# Power.net
KiCad netlist of a schematic drawn in Altium Designer
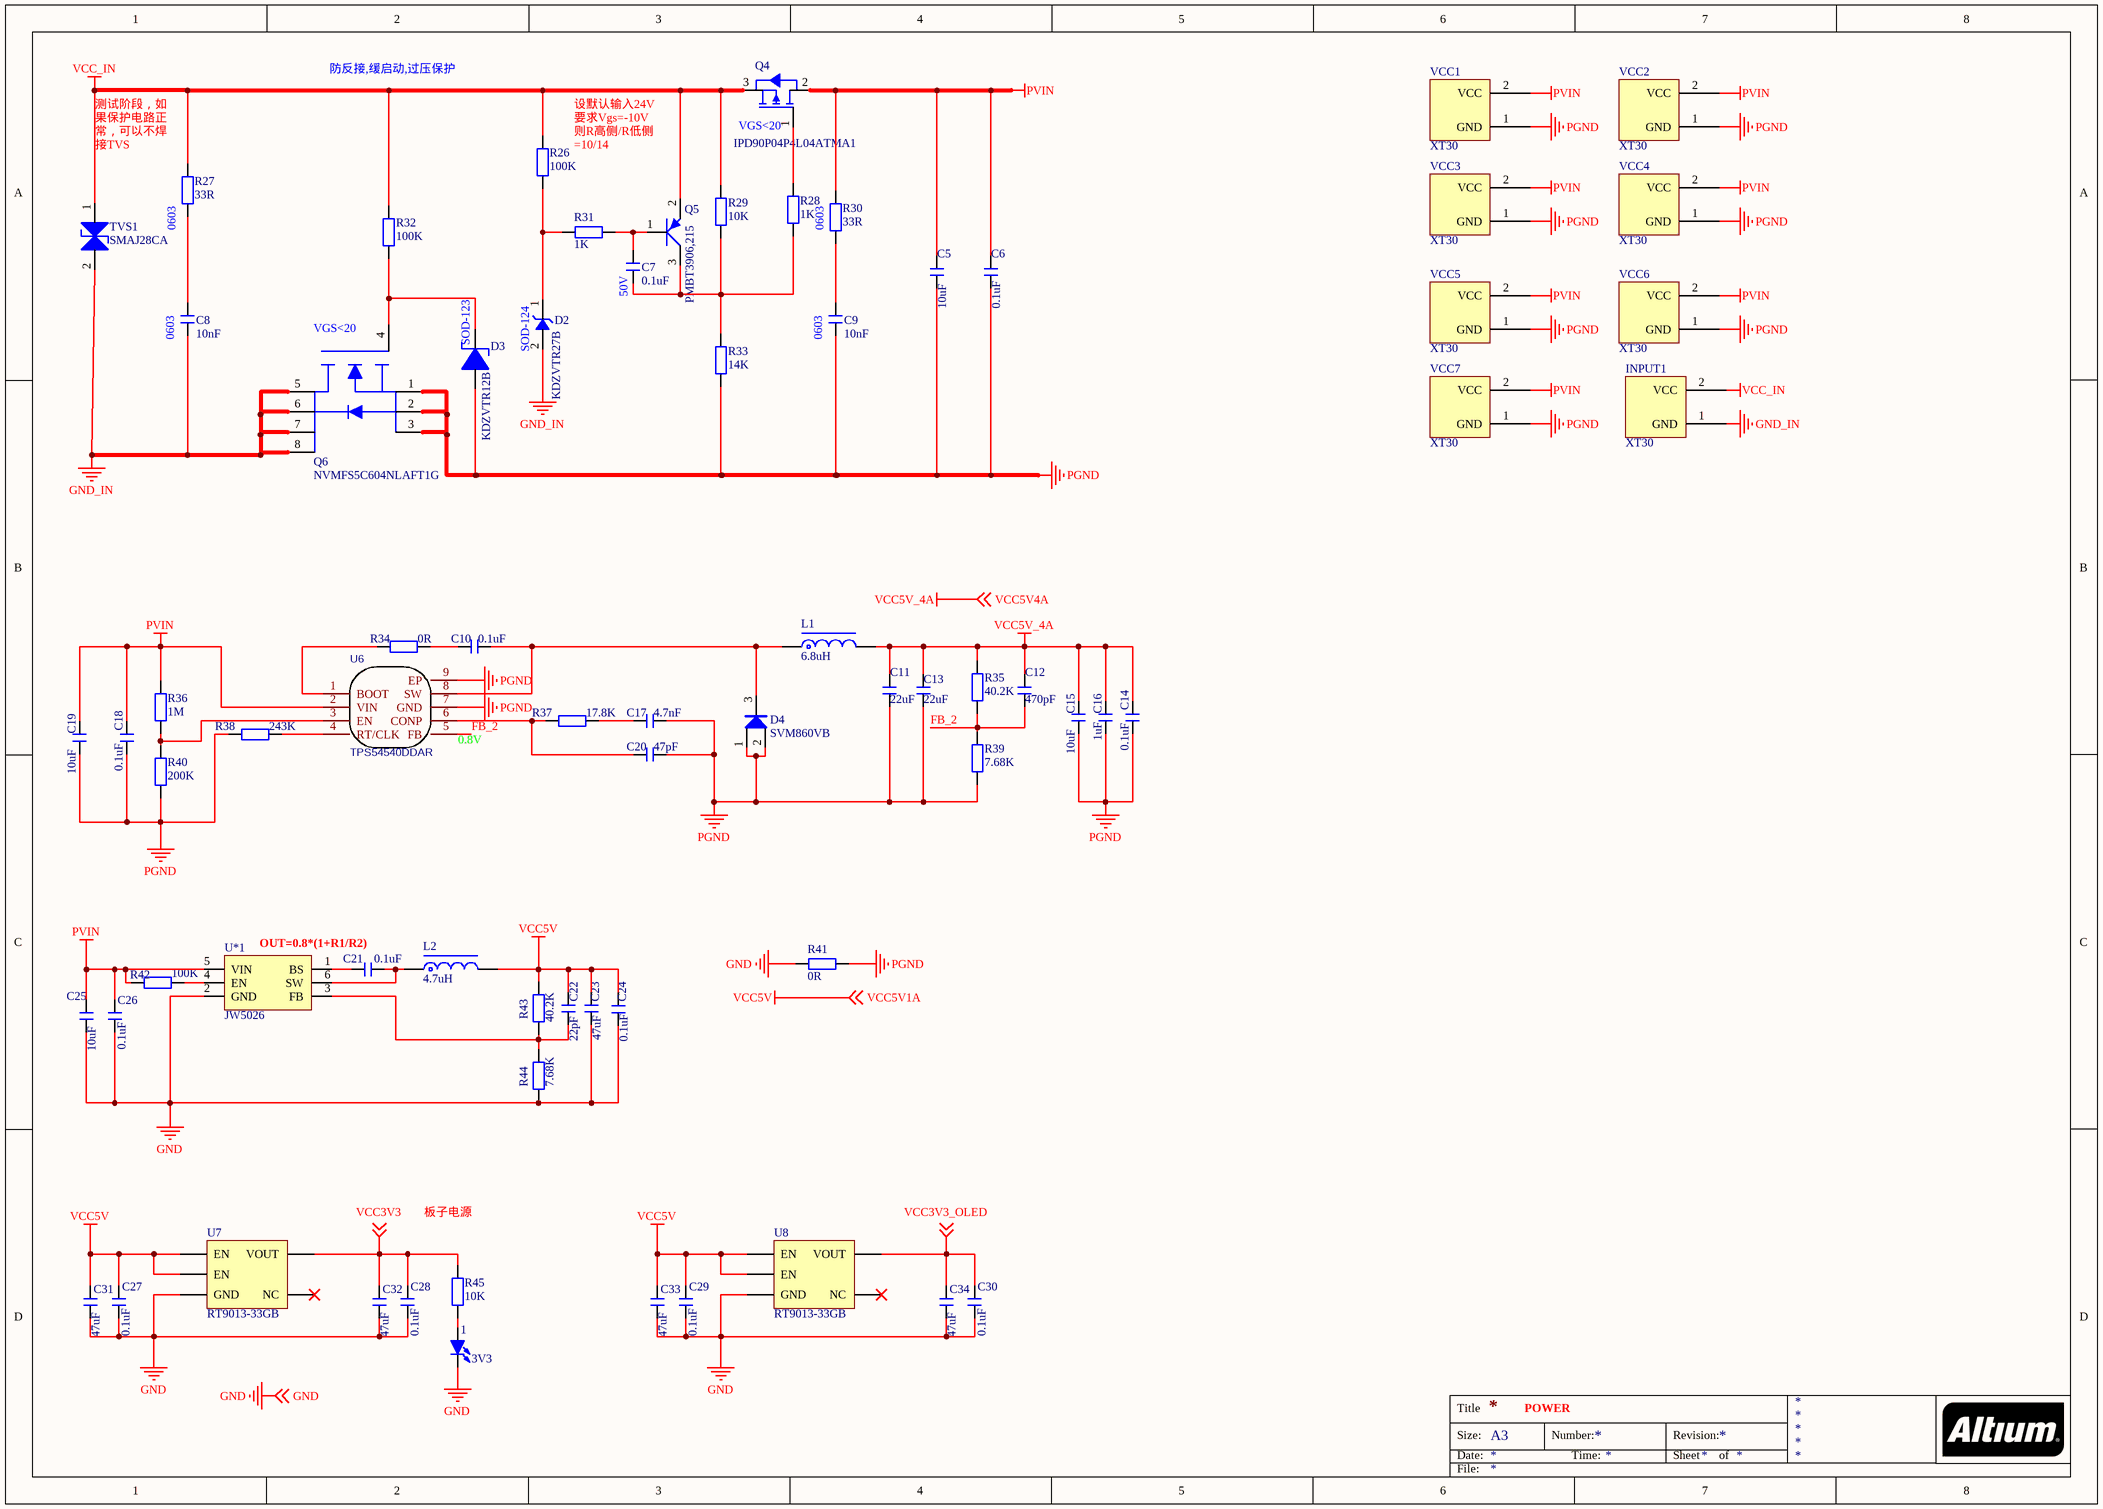
[diagram p0: Power.SchDoc]

(export (version "E")
  (design (tool "Eeschema 10.0.6"))
  (components
    (comp (ref "1")
      (value "3V3")
      (footprint "LED 0805R")
      (description "贴片LED")
      (libsource (lib "0.3 - LED发光二极管") (part "LED-SMD"))
    )
    (comp (ref "C5")
      (value "10uF")
      (footprint "C 0805_L")
      (description "贴片电容")
      (libsource (lib "0.1 - 电阻-电容-电感") (part "C"))
    )
    (comp (ref "C6")
      (value "0.1uF")
      (footprint "C 0805_L")
      (description "贴片电容")
      (libsource (lib "0.1 - 电阻-电容-电感") (part "C"))
    )
    (comp (ref "C7")
      (value "0.1uF")
      (footprint "C 0402_L")
      (description "贴片电容")
      (libsource (lib "0.1 - 电阻-电容-电感") (part "C"))
    )
    (comp (ref "C8")
      (value "10nF")
      (footprint "C 0402_L")
      (description "贴片电容")
      (libsource (lib "0.1 - 电阻-电容-电感") (part "C"))
    )
    (comp (ref "C9")
      (value "10nF")
      (footprint "C 0402_L")
      (description "贴片电容")
      (libsource (lib "0.1 - 电阻-电容-电感") (part "C"))
    )
    (comp (ref "C10")
      (value "0.1uF")
      (footprint "C 0402_L")
      (description "贴片电容")
      (libsource (lib "0.1 - 电阻-电容-电感") (part "C"))
    )
    (comp (ref "C11")
      (value "22uF")
      (footprint "C 0805_L")
      (description "贴片电容")
      (libsource (lib "0.1 - 电阻-电容-电感") (part "C"))
    )
    (comp (ref "C12")
      (value "470pF")
      (footprint "C 0402_L")
      (description "贴片电容")
      (libsource (lib "0.1 - 电阻-电容-电感") (part "C"))
    )
    (comp (ref "C13")
      (value "22uF")
      (footprint "C 0805_L")
      (description "贴片电容")
      (libsource (lib "0.1 - 电阻-电容-电感") (part "C"))
    )
    (comp (ref "C14")
      (value "0.1uF")
      (footprint "C 0805_L")
      (description "贴片电容")
      (libsource (lib "0.1 - 电阻-电容-电感") (part "C"))
    )
    (comp (ref "C15")
      (value "10uF")
      (footprint "C 0805_L")
      (description "贴片电容")
      (libsource (lib "0.1 - 电阻-电容-电感") (part "C"))
    )
    (comp (ref "C16")
      (value "1uF")
      (footprint "C 0805_L")
      (description "贴片电容")
      (libsource (lib "0.1 - 电阻-电容-电感") (part "C"))
    )
    (comp (ref "C17")
      (value "4.7nF")
      (footprint "C 0402_L")
      (description "贴片电容")
      (libsource (lib "0.1 - 电阻-电容-电感") (part "C"))
    )
    (comp (ref "C18")
      (value "0.1uF")
      (footprint "C 0805_L")
      (description "贴片电容")
      (libsource (lib "0.1 - 电阻-电容-电感") (part "C"))
    )
    (comp (ref "C19")
      (value "10uF")
      (footprint "C 0805_L")
      (description "贴片电容")
      (libsource (lib "0.1 - 电阻-电容-电感") (part "C"))
    )
    (comp (ref "C20")
      (value "47pF")
      (footprint "C 0402_L")
      (description "贴片电容")
      (libsource (lib "0.1 - 电阻-电容-电感") (part "C"))
    )
    (comp (ref "C21")
      (value "0.1uF")
      (footprint "C 0402_L")
      (description "贴片电容")
      (libsource (lib "0.1 - 电阻-电容-电感") (part "C"))
    )
    (comp (ref "C22")
      (value "22pF")
      (footprint "C 0402_L")
      (description "贴片电容")
      (libsource (lib "0.1 - 电阻-电容-电感") (part "C"))
    )
    (comp (ref "C23")
      (value "47uF")
      (footprint "C 0805_L")
      (description "贴片电容")
      (libsource (lib "0.1 - 电阻-电容-电感") (part "C"))
    )
    (comp (ref "C24")
      (value "0.1uF")
      (footprint "C 0805_L")
      (description "贴片电容")
      (libsource (lib "0.1 - 电阻-电容-电感") (part "C"))
    )
    (comp (ref "C25")
      (value "10uF")
      (footprint "C 0805_L")
      (description "贴片电容")
      (libsource (lib "0.1 - 电阻-电容-电感") (part "C"))
    )
    (comp (ref "C26")
      (value "0.1uF")
      (footprint "C 0805_L")
      (description "贴片电容")
      (libsource (lib "0.1 - 电阻-电容-电感") (part "C"))
    )
    (comp (ref "C27")
      (value "0.1uF")
      (footprint "C 0805_L")
      (description "贴片电容")
      (libsource (lib "0.1 - 电阻-电容-电感") (part "C"))
    )
    (comp (ref "C28")
      (value "0.1uF")
      (footprint "C 0805_L")
      (description "贴片电容")
      (libsource (lib "0.1 - 电阻-电容-电感") (part "C"))
    )
    (comp (ref "C29")
      (value "0.1uF")
      (footprint "C 0805_L")
      (description "贴片电容")
      (libsource (lib "0.1 - 电阻-电容-电感") (part "C"))
    )
    (comp (ref "C30")
      (value "0.1uF")
      (footprint "C 0805_L")
      (description "贴片电容")
      (libsource (lib "0.1 - 电阻-电容-电感") (part "C"))
    )
    (comp (ref "C31")
      (value "47uF")
      (footprint "C 0805_L")
      (description "贴片电容")
      (libsource (lib "0.1 - 电阻-电容-电感") (part "C"))
    )
    (comp (ref "C32")
      (value "47uF")
      (footprint "C 0805_L")
      (description "贴片电容")
      (libsource (lib "0.1 - 电阻-电容-电感") (part "C"))
    )
    (comp (ref "C33")
      (value "47uF")
      (footprint "C 0805_L")
      (description "贴片电容")
      (libsource (lib "0.1 - 电阻-电容-电感") (part "C"))
    )
    (comp (ref "C34")
      (value "47uF")
      (footprint "C 0805_L")
      (description "贴片电容")
      (libsource (lib "0.1 - 电阻-电容-电感") (part "C"))
    )
    (comp (ref "D2")
      (value "KDZVTR27B")
      (footprint "mx_pcb_library:SOD-123_L2.8-W1.8-LS3.7-RD")
      (libsource (lib "mx_pcb_library") (part "BZD27C30P"))
    )
    (comp (ref "D3")
      (value "KDZVTR12B")
      (footprint "mx_pcb_library:SOD-123_L2.8-W1.8-LS3.7-RD")
      (libsource (lib "mx_pcb_library") (part "KDZVTR12B"))
    )
    (comp (ref "D4")
      (value "SVM860VB")
      (footprint "1.30-二极管-整流桥堆:TO-277B_3P-L6.1-W4.3-LS7.0-BR")
      (description "TO-277B系列,SVM860VB-8A")
      (libsource (lib "0.2 -  二极管-整流桥") (part "SVM860VB"))
    )
    (comp (ref "INPUT1")
      (value "XT30")
      (footprint "mx_pcb_library:XT30PW-M")
      (libsource (lib "mx_pcb_library") (part "XT30"))
    )
    (comp (ref "L1")
      (value "6.8uH")
      (footprint "CDRH73")
      (description "功率屏蔽电感")
      (libsource (lib "0.1 - 电阻-电容-电感") (part "L-CDRH"))
    )
    (comp (ref "L2")
      (value "4.7uH")
      (footprint "CD53")
      (description "CD系列贴片线绕功率电感")
      (libsource (lib "0.1 - 电阻-电容-电感") (part "L-SMD"))
    )
    (comp (ref "Q4")
      (value "IPD90P04P4L04ATMA1")
      (footprint "mx_pcb_library:PG-TO252-3")
      (libsource (lib "mx_pcb_library") (part "IPD90P04P4"))
    )
    (comp (ref "Q5")
      (value "PMBT3906,215")
      (footprint "mx_pcb_library:SOT-23-3_L2.9-W1.3-P1.90-LS2.4-BR")
      (libsource (lib "mx_pcb_library") (part "PMBT3906,215"))
    )
    (comp (ref "Q6")
      (value "NVMFS5C604NLAFT1G")
      (footprint "mx_pcb_library:PG-TDSON-8_L5.0-W6.0-P1.27-LS6.2-BL-EP")
      (libsource (lib "mx_pcb_library") (part "BSC037N08NS5ATMA1"))
    )
    (comp (ref "R26")
      (value "100K")
      (footprint "R 0402_L")
      (description "贴片电阻")
      (libsource (lib "0.1 - 电阻-电容-电感") (part "R"))
    )
    (comp (ref "R27")
      (value "33R")
      (footprint "R 0402_L")
      (description "贴片电阻")
      (libsource (lib "0.1 - 电阻-电容-电感") (part "R"))
    )
    (comp (ref "R28")
      (value "1K")
      (footprint "R 0402_L")
      (description "贴片电阻")
      (libsource (lib "0.1 - 电阻-电容-电感") (part "R"))
    )
    (comp (ref "R29")
      (value "10K")
      (footprint "R 0402_L")
      (description "贴片电阻")
      (libsource (lib "0.1 - 电阻-电容-电感") (part "R"))
    )
    (comp (ref "R30")
      (value "33R")
      (footprint "R 0402_L")
      (description "贴片电阻")
      (libsource (lib "0.1 - 电阻-电容-电感") (part "R"))
    )
    (comp (ref "R31")
      (value "1K")
      (footprint "R 0402_L")
      (description "贴片电阻")
      (libsource (lib "0.1 - 电阻-电容-电感") (part "R"))
    )
    (comp (ref "R32")
      (value "100K")
      (footprint "R 0402_L")
      (description "贴片电阻")
      (libsource (lib "0.1 - 电阻-电容-电感") (part "R"))
    )
    (comp (ref "R33")
      (value "14K")
      (footprint "R 0402_L")
      (description "贴片电阻")
      (libsource (lib "0.1 - 电阻-电容-电感") (part "R"))
    )
    (comp (ref "R34")
      (value "0R")
      (footprint "R 0402_L")
      (description "贴片电阻")
      (libsource (lib "0.1 - 电阻-电容-电感") (part "R"))
    )
    (comp (ref "R35")
      (value "40.2K")
      (footprint "R 0402_L")
      (description "贴片电阻")
      (libsource (lib "0.1 - 电阻-电容-电感") (part "R"))
    )
    (comp (ref "R36")
      (value "1M")
      (footprint "R 0402_L")
      (description "贴片电阻")
      (libsource (lib "0.1 - 电阻-电容-电感") (part "R"))
    )
    (comp (ref "R37")
      (value "17.8K")
      (footprint "R 0402_L")
      (description "贴片电阻")
      (libsource (lib "0.1 - 电阻-电容-电感") (part "R"))
    )
    (comp (ref "R38")
      (value "243K")
      (footprint "R 0402_L")
      (description "贴片电阻")
      (libsource (lib "0.1 - 电阻-电容-电感") (part "R"))
    )
    (comp (ref "R39")
      (value "7.68K")
      (footprint "R 0402_L")
      (description "贴片电阻")
      (libsource (lib "0.1 - 电阻-电容-电感") (part "R"))
    )
    (comp (ref "R40")
      (value "200K")
      (footprint "R 0402_L")
      (description "贴片电阻")
      (libsource (lib "0.1 - 电阻-电容-电感") (part "R"))
    )
    (comp (ref "R41")
      (value "0R")
      (footprint "R 0402_L")
      (description "贴片电阻")
      (libsource (lib "0.1 - 电阻-电容-电感") (part "R"))
    )
    (comp (ref "R42")
      (value "100K")
      (footprint "R 0402_L")
      (description "贴片电阻")
      (libsource (lib "0.1 - 电阻-电容-电感") (part "R"))
    )
    (comp (ref "R43")
      (value "40.2K")
      (footprint "R 0402_L")
      (description "贴片电阻")
      (libsource (lib "0.1 - 电阻-电容-电感") (part "R"))
    )
    (comp (ref "R44")
      (value "7.68K")
      (footprint "R 0402_L")
      (description "贴片电阻")
      (libsource (lib "0.1 - 电阻-电容-电感") (part "R"))
    )
    (comp (ref "R45")
      (value "10K")
      (footprint "R 0402_L")
      (description "贴片电阻")
      (libsource (lib "0.1 - 电阻-电容-电感") (part "R"))
    )
    (comp (ref "TVS1")
      (value "SMAJ28CA")
      (footprint "mx_pcb_library:SMA(DO-214AC)")
      (libsource (lib "mx_pcb_library") (part "SMAJ28CA"))
    )
    (comp (ref "U*1")
      (value "JW5026")
      (footprint "SOT-23-6_L2.9-W1.6-P0.95-LS2.8-BL")
      (description "BUCK、MAX40V")
      (libsource (lib "mx_pcb_library") (part "JW5026"))
    )
    (comp (ref "U6")
      (value "TPS54540DDAR")
      (footprint "mx_pcb_library:TPS54540")
      (fields (field (name "BOM_SUPPLIER PART") "C95286"))
      (libsource (lib "mx_pcb_library") (part "TPS54540DDAR"))
    )
    (comp (ref "U7")
      (value "RT9013-33GB")
      (footprint "SOT23-5M")
      (libsource (lib "mx_pcb_library") (part "RT9013-33GB"))
    )
    (comp (ref "U8")
      (value "RT9013-33GB")
      (footprint "SOT23-5M")
      (libsource (lib "mx_pcb_library") (part "RT9013-33GB"))
    )
    (comp (ref "VCC1")
      (value "XT30")
      (footprint "mx_pcb_library:XT30UPB-F")
      (libsource (lib "mx_pcb_library") (part "XT30"))
    )
    (comp (ref "VCC2")
      (value "XT30")
      (footprint "mx_pcb_library:XT30UPB-F")
      (libsource (lib "mx_pcb_library") (part "XT30"))
    )
    (comp (ref "VCC3")
      (value "XT30")
      (footprint "mx_pcb_library:XT30UPB-F")
      (libsource (lib "mx_pcb_library") (part "XT30"))
    )
    (comp (ref "VCC4")
      (value "XT30")
      (footprint "mx_pcb_library:XT30UPB-F")
      (libsource (lib "mx_pcb_library") (part "XT30"))
    )
    (comp (ref "VCC5")
      (value "XT30")
      (footprint "mx_pcb_library:XT30UPB-F")
      (libsource (lib "mx_pcb_library") (part "XT30"))
    )
    (comp (ref "VCC6")
      (value "XT30")
      (footprint "mx_pcb_library:XT30UPB-F")
      (libsource (lib "mx_pcb_library") (part "XT30"))
    )
    (comp (ref "VCC7")
      (value "XT30")
      (footprint "mx_pcb_library:XT30UPB-F")
      (libsource (lib "mx_pcb_library") (part "XT30"))
    )
  )
  (nets
    (net (code "1") (name "/FB_2") (class "Default")
      (node (ref "C12") (pin "1") (pinfunction "1_1") (pintype "passive"))
      (node (ref "R35") (pin "1") (pinfunction "1_1") (pintype "passive"))
      (node (ref "R39") (pin "2") (pinfunction "2_2") (pintype "passive"))
      (node (ref "U6") (pin "5") (pinfunction "FB_5") (pintype "passive"))
    )
    (net (code "2") (name "GND") (class "Default")
      (node (ref "1") (pin "2") (pinfunction "K_2") (pintype "passive"))
      (node (ref "C23") (pin "1") (pinfunction "1_1") (pintype "passive"))
      (node (ref "C24") (pin "1") (pinfunction "1_1") (pintype "passive"))
      (node (ref "C25") (pin "1") (pinfunction "1_1") (pintype "passive"))
      (node (ref "C26") (pin "1") (pinfunction "1_1") (pintype "passive"))
      (node (ref "C27") (pin "1") (pinfunction "1_1") (pintype "passive"))
      (node (ref "C28") (pin "1") (pinfunction "1_1") (pintype "passive"))
      (node (ref "C29") (pin "1") (pinfunction "1_1") (pintype "passive"))
      (node (ref "C30") (pin "1") (pinfunction "1_1") (pintype "passive"))
      (node (ref "C31") (pin "1") (pinfunction "1_1") (pintype "passive"))
      (node (ref "C32") (pin "1") (pinfunction "1_1") (pintype "passive"))
      (node (ref "C33") (pin "1") (pinfunction "1_1") (pintype "passive"))
      (node (ref "C34") (pin "1") (pinfunction "1_1") (pintype "passive"))
      (node (ref "R41") (pin "1") (pinfunction "1_1") (pintype "passive"))
      (node (ref "R44") (pin "1") (pinfunction "1_1") (pintype "passive"))
      (node (ref "U*1") (pin "2") (pinfunction "GND_2") (pintype "passive"))
      (node (ref "U7") (pin "2") (pinfunction "GND_2") (pintype "passive"))
      (node (ref "U8") (pin "2") (pinfunction "GND_2") (pintype "passive"))
    )
    (net (code "3") (name "GND_IN") (class "Default")
      (node (ref "C8") (pin "1") (pinfunction "1_1") (pintype "passive"))
      (node (ref "D2") (pin "2") (pinfunction "2_2") (pintype "passive"))
      (node (ref "INPUT1") (pin "1") (pinfunction "GND_1") (pintype "passive"))
      (node (ref "Q6") (pin "5") (pinfunction "5_5") (pintype "passive"))
      (node (ref "Q6") (pin "6") (pinfunction "6_6") (pintype "passive"))
      (node (ref "Q6") (pin "7") (pinfunction "7_7") (pintype "passive"))
      (node (ref "Q6") (pin "8") (pinfunction "8_8") (pintype "passive"))
      (node (ref "TVS1") (pin "2") (pinfunction "2_2") (pintype "passive"))
    )
    (net (code "4") (name "Net-(1-A)") (class "Default")
      (node (ref "1") (pin "1") (pinfunction "A_1") (pintype "passive"))
      (node (ref "R45") (pin "2") (pinfunction "2_2") (pintype "passive"))
    )
    (net (code "5") (name "Net-(C7-Pad1)") (class "Default")
      (node (ref "C7") (pin "1") (pinfunction "1_1") (pintype "passive"))
      (node (ref "Q5") (pin "3") (pinfunction "3_3") (pintype "passive"))
      (node (ref "R28") (pin "1") (pinfunction "1_1") (pintype "passive"))
      (node (ref "R29") (pin "1") (pinfunction "1_1") (pintype "passive"))
      (node (ref "R33") (pin "2") (pinfunction "2_2") (pintype "passive"))
    )
    (net (code "6") (name "Net-(C7-Pad2)") (class "Default")
      (node (ref "C7") (pin "2") (pinfunction "2_2") (pintype "passive"))
      (node (ref "Q5") (pin "1") (pinfunction "1_1") (pintype "passive"))
      (node (ref "R31") (pin "1") (pinfunction "1_1") (pintype "passive"))
    )
    (net (code "7") (name "Net-(C8-Pad2)") (class "Default")
      (node (ref "C8") (pin "2") (pinfunction "2_2") (pintype "passive"))
      (node (ref "R27") (pin "1") (pinfunction "1_1") (pintype "passive"))
    )
    (net (code "8") (name "Net-(C9-Pad2)") (class "Default")
      (node (ref "C9") (pin "2") (pinfunction "2_2") (pintype "passive"))
      (node (ref "R30") (pin "1") (pinfunction "1_1") (pintype "passive"))
    )
    (net (code "9") (name "Net-(C10-Pad1)") (class "Default")
      (node (ref "C10") (pin "1") (pinfunction "1_1") (pintype "passive"))
      (node (ref "R34") (pin "1") (pinfunction "1_1") (pintype "passive"))
    )
    (net (code "10") (name "Net-(C17-Pad1)") (class "Default")
      (node (ref "C17") (pin "1") (pinfunction "1_1") (pintype "passive"))
      (node (ref "R37") (pin "1") (pinfunction "1_1") (pintype "passive"))
    )
    (net (code "11") (name "Net-(D2-Pad1)") (class "Default")
      (node (ref "D2") (pin "1") (pinfunction "1_1") (pintype "passive"))
      (node (ref "R26") (pin "1") (pinfunction "1_1") (pintype "passive"))
      (node (ref "R31") (pin "2") (pinfunction "2_2") (pintype "passive"))
    )
    (net (code "12") (name "Net-(D3-Pad1)") (class "Default")
      (node (ref "D3") (pin "1") (pinfunction "1_1") (pintype "passive"))
      (node (ref "Q6") (pin "4") (pinfunction "4_4") (pintype "passive"))
      (node (ref "R32") (pin "1") (pinfunction "1_1") (pintype "passive"))
    )
    (net (code "13") (name "Net-(Q4-Pad1)") (class "Default")
      (node (ref "Q4") (pin "1") (pinfunction "1_1") (pintype "passive"))
      (node (ref "R28") (pin "2") (pinfunction "2_2") (pintype "passive"))
    )
    (net (code "14") (name "Net-(U*1-BS)") (class "Default")
      (node (ref "C21") (pin "1") (pinfunction "1_1") (pintype "passive"))
      (node (ref "U*1") (pin "1") (pinfunction "BS_1") (pintype "passive"))
    )
    (net (code "15") (name "Net-(U*1-EN)") (class "Default")
      (node (ref "R42") (pin "1") (pinfunction "1_1") (pintype "passive"))
      (node (ref "U*1") (pin "4") (pinfunction "EN_4") (pintype "passive"))
    )
    (net (code "16") (name "Net-(U*1-FB)") (class "Default")
      (node (ref "C22") (pin "1") (pinfunction "1_1") (pintype "passive"))
      (node (ref "R43") (pin "1") (pinfunction "1_1") (pintype "passive"))
      (node (ref "R44") (pin "2") (pinfunction "2_2") (pintype "passive"))
      (node (ref "U*1") (pin "3") (pinfunction "FB_3") (pintype "passive"))
    )
    (net (code "17") (name "Net-(U*1-SW)") (class "Default")
      (node (ref "C21") (pin "2") (pinfunction "2_2") (pintype "passive"))
      (node (ref "L2") (pin "1") (pinfunction "1_1") (pintype "passive"))
      (node (ref "U*1") (pin "6") (pinfunction "SW_6") (pintype "passive"))
    )
    (net (code "18") (name "Net-(U6-BOOT)") (class "Default")
      (node (ref "R34") (pin "2") (pinfunction "2_2") (pintype "passive"))
      (node (ref "U6") (pin "1") (pinfunction "BOOT_1") (pintype "passive"))
    )
    (net (code "19") (name "Net-(U6-CONP)") (class "Default")
      (node (ref "C20") (pin "1") (pinfunction "1_1") (pintype "passive"))
      (node (ref "R37") (pin "2") (pinfunction "2_2") (pintype "passive"))
      (node (ref "U6") (pin "6") (pinfunction "CONP_6") (pintype "passive"))
    )
    (net (code "20") (name "Net-(U6-EN)") (class "Default")
      (node (ref "R36") (pin "1") (pinfunction "1_1") (pintype "passive"))
      (node (ref "R40") (pin "2") (pinfunction "2_2") (pintype "passive"))
      (node (ref "U6") (pin "3") (pinfunction "EN_3") (pintype "passive"))
    )
    (net (code "21") (name "Net-(U6-RT{slash}CLK)") (class "Default")
      (node (ref "R38") (pin "1") (pinfunction "1_1") (pintype "passive"))
      (node (ref "U6") (pin "4") (pinfunction "RT/CLK_4") (pintype "passive"))
    )
    (net (code "22") (name "Net-(U6-SW)") (class "Default")
      (node (ref "C10") (pin "2") (pinfunction "2_2") (pintype "passive"))
      (node (ref "D4") (pin "3") (pinfunction "3_3") (pintype "passive"))
      (node (ref "L1") (pin "1") (pinfunction "1_1") (pintype "passive"))
      (node (ref "U6") (pin "8") (pinfunction "SW_8") (pintype "passive"))
    )
    (net (code "23") (name "PGND") (class "Default")
      (node (ref "C11") (pin "1") (pinfunction "1_1") (pintype "passive"))
      (node (ref "C13") (pin "1") (pinfunction "1_1") (pintype "passive"))
      (node (ref "C14") (pin "1") (pinfunction "1_1") (pintype "passive"))
      (node (ref "C15") (pin "1") (pinfunction "1_1") (pintype "passive"))
      (node (ref "C16") (pin "1") (pinfunction "1_1") (pintype "passive"))
      (node (ref "C17") (pin "2") (pinfunction "2_2") (pintype "passive"))
      (node (ref "C18") (pin "1") (pinfunction "1_1") (pintype "passive"))
      (node (ref "C19") (pin "1") (pinfunction "1_1") (pintype "passive"))
      (node (ref "C20") (pin "2") (pinfunction "2_2") (pintype "passive"))
      (node (ref "C5") (pin "2") (pinfunction "2_2") (pintype "passive"))
      (node (ref "C6") (pin "2") (pinfunction "2_2") (pintype "passive"))
      (node (ref "C9") (pin "1") (pinfunction "1_1") (pintype "passive"))
      (node (ref "D3") (pin "2") (pinfunction "2_2") (pintype "passive"))
      (node (ref "D4") (pin "1") (pinfunction "A_1") (pintype "passive"))
      (node (ref "D4") (pin "2") (pinfunction "K_2") (pintype "passive"))
      (node (ref "Q6") (pin "1") (pinfunction "1_1") (pintype "passive"))
      (node (ref "Q6") (pin "2") (pinfunction "2_2") (pintype "passive"))
      (node (ref "Q6") (pin "3") (pinfunction "3_3") (pintype "passive"))
      (node (ref "R33") (pin "1") (pinfunction "1_1") (pintype "passive"))
      (node (ref "R38") (pin "2") (pinfunction "2_2") (pintype "passive"))
      (node (ref "R39") (pin "1") (pinfunction "1_1") (pintype "passive"))
      (node (ref "R40") (pin "1") (pinfunction "1_1") (pintype "passive"))
      (node (ref "R41") (pin "2") (pinfunction "2_2") (pintype "passive"))
      (node (ref "U6") (pin "7") (pinfunction "GND_7") (pintype "passive"))
      (node (ref "U6") (pin "9") (pinfunction "EP_9") (pintype "passive"))
      (node (ref "VCC1") (pin "1") (pinfunction "GND_1") (pintype "passive"))
      (node (ref "VCC2") (pin "1") (pinfunction "GND_1") (pintype "passive"))
      (node (ref "VCC3") (pin "1") (pinfunction "GND_1") (pintype "passive"))
      (node (ref "VCC4") (pin "1") (pinfunction "GND_1") (pintype "passive"))
      (node (ref "VCC5") (pin "1") (pinfunction "GND_1") (pintype "passive"))
      (node (ref "VCC6") (pin "1") (pinfunction "GND_1") (pintype "passive"))
      (node (ref "VCC7") (pin "1") (pinfunction "GND_1") (pintype "passive"))
    )
    (net (code "24") (name "PVIN") (class "Default")
      (node (ref "C18") (pin "2") (pinfunction "2_2") (pintype "passive"))
      (node (ref "C19") (pin "2") (pinfunction "2_2") (pintype "passive"))
      (node (ref "C25") (pin "2") (pinfunction "2_2") (pintype "passive"))
      (node (ref "C26") (pin "2") (pinfunction "2_2") (pintype "passive"))
      (node (ref "C5") (pin "1") (pinfunction "1_1") (pintype "passive"))
      (node (ref "C6") (pin "1") (pinfunction "1_1") (pintype "passive"))
      (node (ref "Q4") (pin "2") (pinfunction "2_2") (pintype "passive"))
      (node (ref "R30") (pin "2") (pinfunction "2_2") (pintype "passive"))
      (node (ref "R36") (pin "2") (pinfunction "2_2") (pintype "passive"))
      (node (ref "R42") (pin "2") (pinfunction "2_2") (pintype "passive"))
      (node (ref "U*1") (pin "5") (pinfunction "VIN_5") (pintype "passive"))
      (node (ref "U6") (pin "2") (pinfunction "VIN_2") (pintype "passive"))
      (node (ref "VCC1") (pin "2") (pinfunction "VCC_2") (pintype "passive"))
      (node (ref "VCC2") (pin "2") (pinfunction "VCC_2") (pintype "passive"))
      (node (ref "VCC3") (pin "2") (pinfunction "VCC_2") (pintype "passive"))
      (node (ref "VCC4") (pin "2") (pinfunction "VCC_2") (pintype "passive"))
      (node (ref "VCC5") (pin "2") (pinfunction "VCC_2") (pintype "passive"))
      (node (ref "VCC6") (pin "2") (pinfunction "VCC_2") (pintype "passive"))
      (node (ref "VCC7") (pin "2") (pinfunction "VCC_2") (pintype "passive"))
    )
    (net (code "25") (name "VCC3V3") (class "Default")
      (node (ref "C28") (pin "2") (pinfunction "2_2") (pintype "passive"))
      (node (ref "C32") (pin "2") (pinfunction "2_2") (pintype "passive"))
      (node (ref "R45") (pin "1") (pinfunction "1_1") (pintype "passive"))
      (node (ref "U7") (pin "5") (pinfunction "VOUT_5") (pintype "passive"))
    )
    (net (code "26") (name "VCC3V3_OLED") (class "Default")
      (node (ref "C30") (pin "2") (pinfunction "2_2") (pintype "passive"))
      (node (ref "C34") (pin "2") (pinfunction "2_2") (pintype "passive"))
      (node (ref "U8") (pin "5") (pinfunction "VOUT_5") (pintype "passive"))
    )
    (net (code "27") (name "VCC5V") (class "Default")
      (node (ref "C22") (pin "2") (pinfunction "2_2") (pintype "passive"))
      (node (ref "C23") (pin "2") (pinfunction "2_2") (pintype "passive"))
      (node (ref "C24") (pin "2") (pinfunction "2_2") (pintype "passive"))
      (node (ref "C27") (pin "2") (pinfunction "2_2") (pintype "passive"))
      (node (ref "C29") (pin "2") (pinfunction "2_2") (pintype "passive"))
      (node (ref "C31") (pin "2") (pinfunction "2_2") (pintype "passive"))
      (node (ref "C33") (pin "2") (pinfunction "2_2") (pintype "passive"))
      (node (ref "L2") (pin "2") (pinfunction "2_2") (pintype "passive"))
      (node (ref "R43") (pin "2") (pinfunction "2_2") (pintype "passive"))
      (node (ref "U7") (pin "1") (pinfunction "EN_1") (pintype "passive"))
      (node (ref "U7") (pin "3") (pinfunction "EN_3") (pintype "passive"))
      (node (ref "U8") (pin "1") (pinfunction "EN_1") (pintype "passive"))
      (node (ref "U8") (pin "3") (pinfunction "EN_3") (pintype "passive"))
    )
    (net (code "28") (name "VCC5V4A") (class "Default")
      (node (ref "C11") (pin "2") (pinfunction "2_2") (pintype "passive"))
      (node (ref "C12") (pin "2") (pinfunction "2_2") (pintype "passive"))
      (node (ref "C13") (pin "2") (pinfunction "2_2") (pintype "passive"))
      (node (ref "C14") (pin "2") (pinfunction "2_2") (pintype "passive"))
      (node (ref "C15") (pin "2") (pinfunction "2_2") (pintype "passive"))
      (node (ref "C16") (pin "2") (pinfunction "2_2") (pintype "passive"))
      (node (ref "L1") (pin "2") (pinfunction "2_2") (pintype "passive"))
      (node (ref "R35") (pin "2") (pinfunction "2_2") (pintype "passive"))
    )
    (net (code "29") (name "VCC_IN") (class "Default")
      (node (ref "INPUT1") (pin "2") (pinfunction "VCC_2") (pintype "passive"))
      (node (ref "Q4") (pin "3") (pinfunction "3_3") (pintype "passive"))
      (node (ref "Q5") (pin "2") (pinfunction "2_2") (pintype "passive"))
      (node (ref "R26") (pin "2") (pinfunction "2_2") (pintype "passive"))
      (node (ref "R27") (pin "2") (pinfunction "2_2") (pintype "passive"))
      (node (ref "R29") (pin "2") (pinfunction "2_2") (pintype "passive"))
      (node (ref "R32") (pin "2") (pinfunction "2_2") (pintype "passive"))
      (node (ref "TVS1") (pin "1") (pinfunction "1_1") (pintype "passive"))
    )
    (net (code "30") (name "unconnected-(U7-NC-Pad4)") (class "Default")
      (node (ref "U7") (pin "4") (pinfunction "NC_4") (pintype "passive+no_connect"))
    )
    (net (code "31") (name "unconnected-(U8-NC-Pad4)") (class "Default")
      (node (ref "U8") (pin "4") (pinfunction "NC_4") (pintype "passive+no_connect"))
    )
  )
)
